# CH32X315CCU-R0.net
KiCad netlist of a schematic drawn in Altium Designer
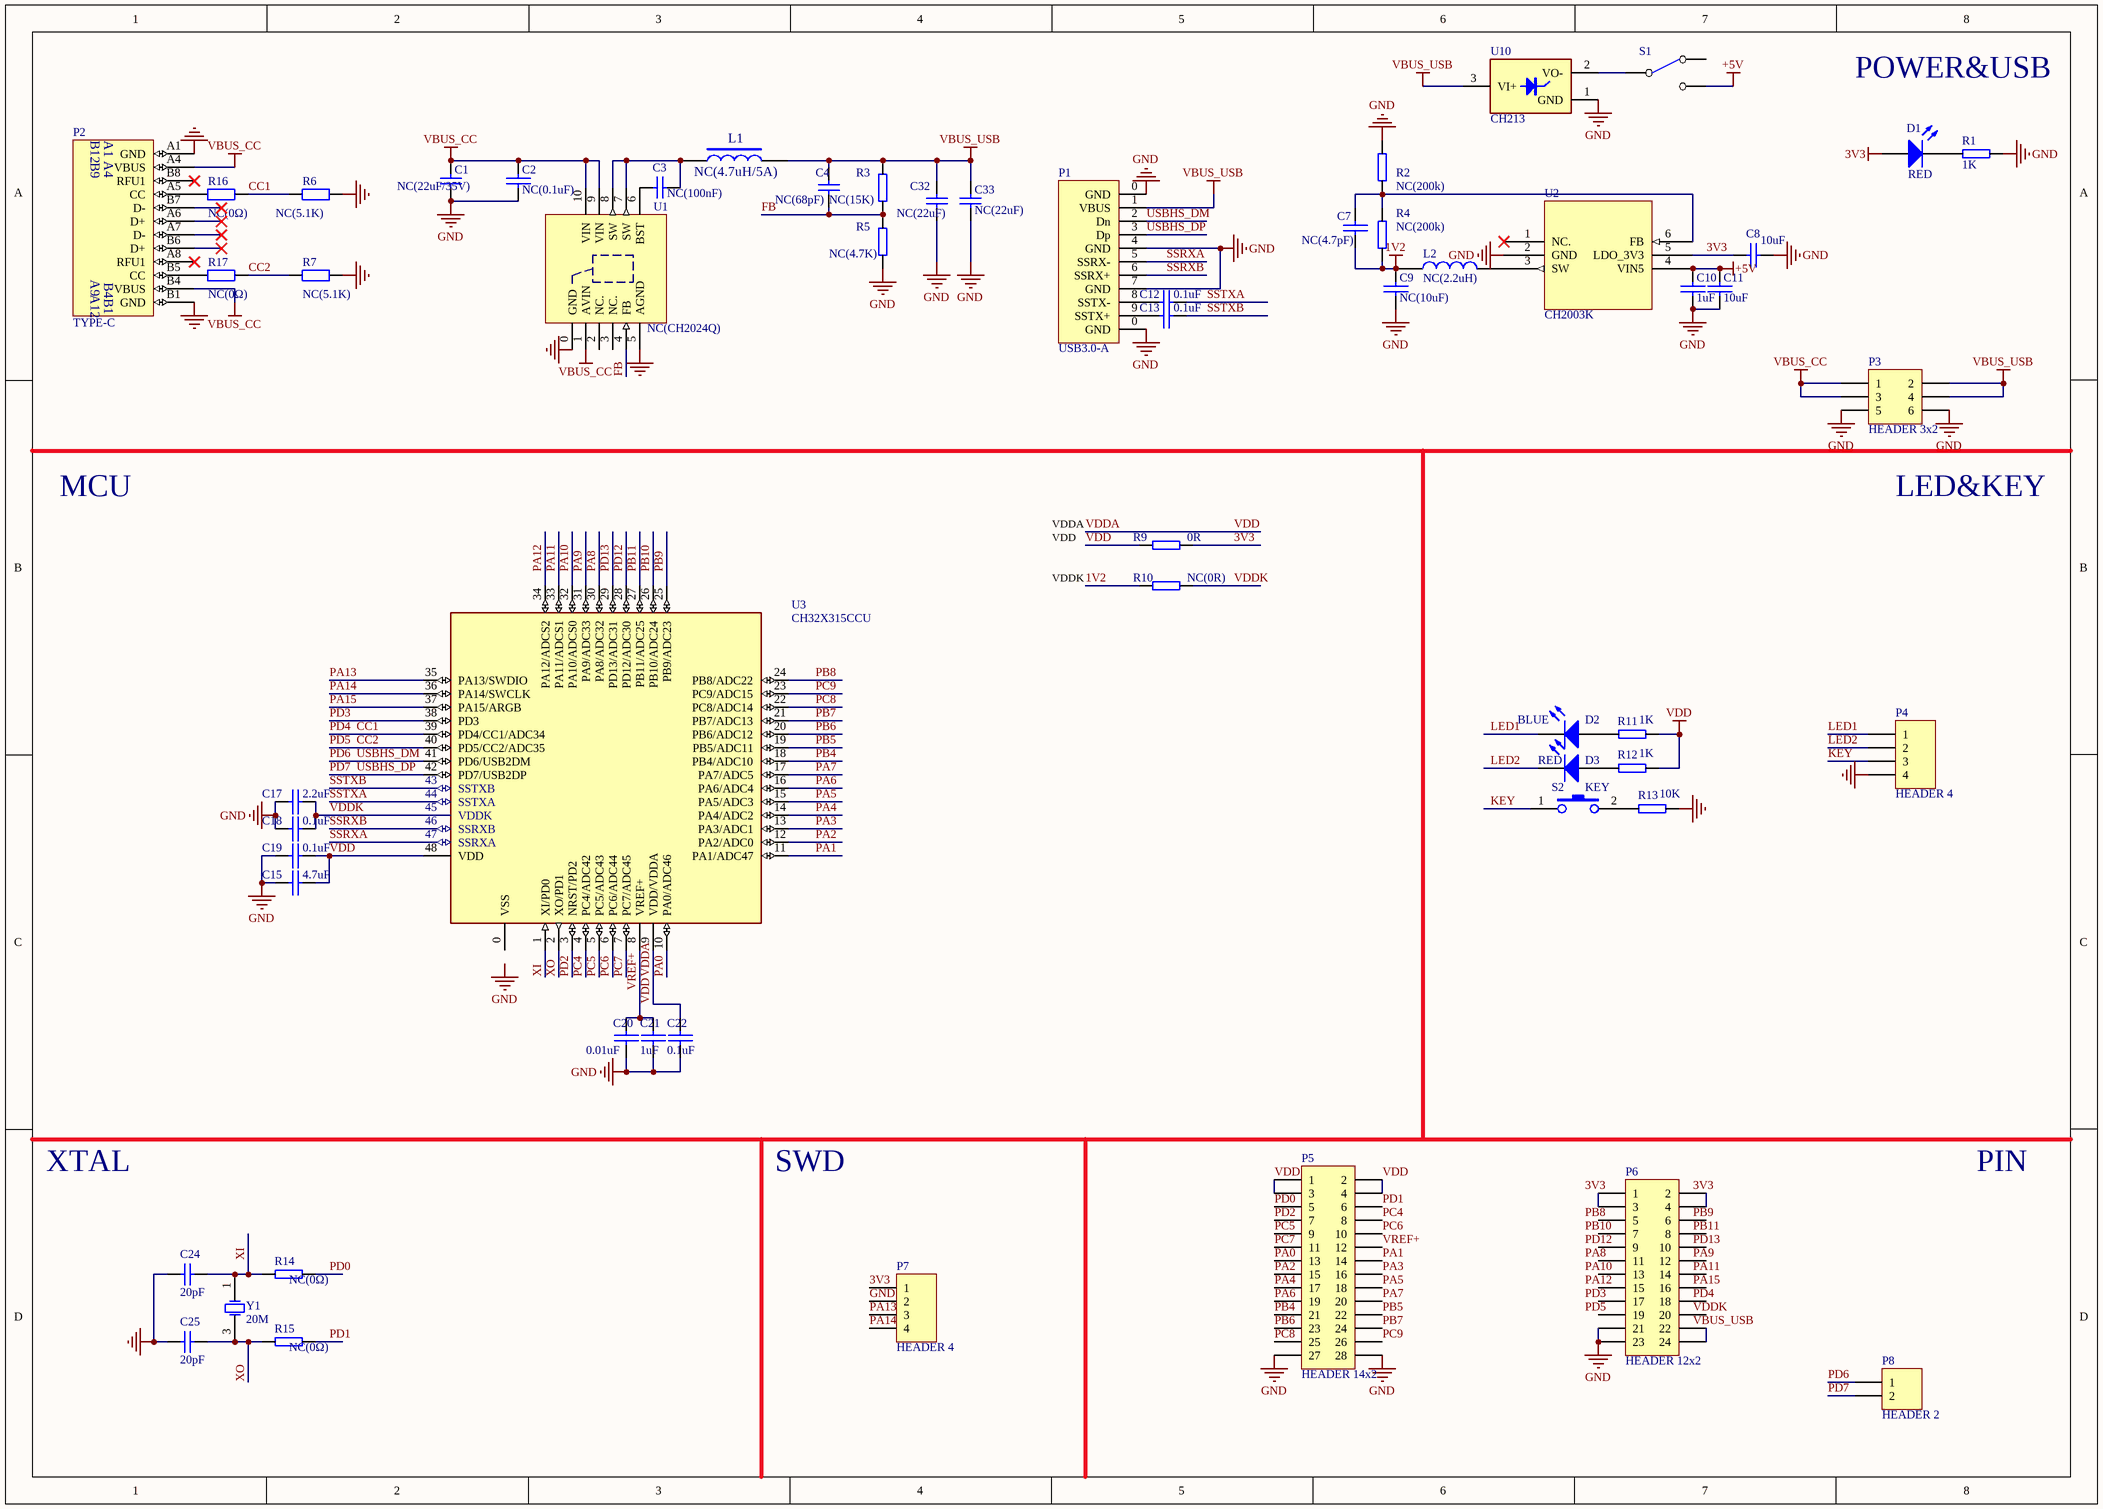
[diagram p0: CH32X315CCU-R0.SchDoc]

(export (version "E")
  (design (tool "Eeschema 10.0.6"))
  (components
    (comp (ref "C1")
      (value "NC(22uF/35V)")
      (footprint "0805_C")
      (description "贴片电容")
      (libsource (lib "Miscellaneous Devices LC") (part "0603 100nF (104) 10% 50V"))
    )
    (comp (ref "C2")
      (value "NC(0.1uF)")
      (footprint "0402_C")
      (description "Capacitor")
      (libsource (lib "*") (part "CAP"))
    )
    (comp (ref "C3")
      (value "NC(100nF)")
      (footprint "0402_C")
      (description "贴片电容")
      (libsource (lib "Miscellaneous Devices LC") (part "0603 1uF (105) 10% 50V"))
    )
    (comp (ref "C4")
      (value "NC(68pF)")
      (footprint "0402_C")
      (description "贴片电容")
      (libsource (lib "Miscellaneous Devices LC") (part "0603 100nF (104) 10% 50V"))
    )
    (comp (ref "C7")
      (value "NC(4.7pF)")
      (footprint "0402_C")
      (description "Capacitor")
      (libsource (lib "") (part "CAP_1"))
    )
    (comp (ref "C8")
      (value "10uF")
      (footprint "0603_C")
      (description "Capacitor")
      (libsource (lib "*") (part "CAP"))
    )
    (comp (ref "C9")
      (value "NC(10uF)")
      (footprint "0603_C")
      (description "Capacitor")
      (libsource (lib "*") (part "CAP"))
    )
    (comp (ref "C10")
      (value "1uF")
      (footprint "0402_C")
      (description "Capacitor")
      (libsource (lib "") (part "CAP_1"))
    )
    (comp (ref "C11")
      (value "10uF")
      (footprint "0603_C")
      (description "Capacitor")
      (libsource (lib "*") (part "CAP"))
    )
    (comp (ref "C12")
      (value "0.1uF")
      (footprint "0402_C")
      (description "Capacitor")
      (libsource (lib "*") (part "CAP"))
    )
    (comp (ref "C13")
      (value "0.1uF")
      (footprint "0402_C")
      (description "Capacitor")
      (libsource (lib "*") (part "CAP"))
    )
    (comp (ref "C15")
      (value "4.7uF")
      (footprint "0402_C")
      (description "Capacitor")
      (libsource (lib "") (part "CAP_1"))
    )
    (comp (ref "C17")
      (value "2.2uF")
      (footprint "0402_C")
      (description "Capacitor")
      (libsource (lib "") (part "CAP_1"))
    )
    (comp (ref "C18")
      (value "0.1uF")
      (footprint "0402_C")
      (description "Capacitor")
      (libsource (lib "") (part "CAP_1"))
    )
    (comp (ref "C19")
      (value "0.1uF")
      (footprint "0402_C")
      (description "Capacitor")
      (libsource (lib "") (part "CAP_1"))
    )
    (comp (ref "C20")
      (value "0.01uF")
      (footprint "0402_C")
      (description "Capacitor")
      (libsource (lib "") (part "CAP_1"))
    )
    (comp (ref "C21")
      (value "1uF")
      (footprint "0402_C")
      (description "Capacitor")
      (libsource (lib "") (part "CAP_1"))
    )
    (comp (ref "C22")
      (value "0.1uF")
      (footprint "0402_C")
      (description "Capacitor")
      (libsource (lib "") (part "CAP_1"))
    )
    (comp (ref "C24")
      (value "20pF")
      (footprint "0402_C")
      (description "Capacitor")
      (libsource (lib "Miscellaneous Devices") (part "Cap"))
    )
    (comp (ref "C25")
      (value "20pF")
      (footprint "0402_C")
      (description "Capacitor")
      (libsource (lib "Miscellaneous Devices") (part "Cap"))
    )
    (comp (ref "C32")
      (value "NC(22uF)")
      (footprint "0805_C")
      (description "贴片电容")
      (libsource (lib "Miscellaneous Devices LC") (part "0603 100nF (104) 10% 50V"))
    )
    (comp (ref "C33")
      (value "NC(22uF)")
      (footprint "0805_C")
      (description "贴片电容")
      (libsource (lib "Miscellaneous Devices LC") (part "0603 100nF (104) 10% 50V"))
    )
    (comp (ref "D1")
      (value "RED")
      (footprint "0603+")
      (description "Typical INFRARED GaAs LED")
      (fields (field (name "PUBLISHER") "Altium Limited"))
      (libsource (lib "*") (part "LED0"))
    )
    (comp (ref "D2")
      (value "BLUE")
      (footprint "0603+")
      (description "Typical INFRARED GaAs LED")
      (fields (field (name "PUBLISHER") "Altium Limited"))
      (libsource (lib "*") (part "LED0"))
    )
    (comp (ref "D3")
      (value "RED")
      (footprint "0603+")
      (description "Typical INFRARED GaAs LED")
      (fields (field (name "PUBLISHER") "Altium Limited"))
      (libsource (lib "*") (part "LED0"))
    )
    (comp (ref "L1")
      (value "NC(4.7uH/5A)")
      (footprint "IND-SMD_L7.0-W6.6")
      (libsource (lib "wch_sch_others") (part "INDUCTOR"))
    )
    (comp (ref "L2") (value "NC(2.2uH)") (footprint "CD32") (libsource (lib "*") (part "INDUCTOR")))
    (comp (ref "P1")
      (value "USB3.0-A")
      (footprint "USB3.0-A-Receptacle")
      (libsource (lib "wch_sch_others") (part "USB3.0-A"))
    )
    (comp (ref "P2")
      (value "TYPE-C")
      (footprint "TYPE-C-Receptacle-2.0")
      (libsource (lib "*") (part "TYPE-C1"))
    )
    (comp (ref "P3")
      (value "HEADER 3x2")
      (footprint "MYPCB:IDC6-2.54mm")
      (description "Header, 3-Pin, Dual row")
      (libsource (lib "wch_sch_others") (part "HEADER 3x2"))
    )
    (comp (ref "P4")
      (value "HEADER 4")
      (footprint "SIP4-2.54mm")
      (description "Header, 4-Pin")
      (libsource (lib "wch_sch_others") (part "HEADER 4"))
    )
    (comp (ref "P5")
      (value "HEADER 14x2")
      (footprint "MYPCB:IDC28-2.54MM")
      (description "Header, 14-Pin, Dual row")
      (libsource (lib "wch_sch_others") (part "HEADER 14x2"))
    )
    (comp (ref "P6")
      (value "HEADER 12x2")
      (footprint "MYPCB:IDC24-2.54MM")
      (description "Header, 12-Pin, Dual row")
      (libsource (lib "wch_sch_others") (part "HEADER 12x2"))
    )
    (comp (ref "P7")
      (value "HEADER 4")
      (footprint "SIP4-2.54mm")
      (description "Header, 4-Pin")
      (libsource (lib "wch_sch_others") (part "HEADER 4"))
    )
    (comp (ref "P8")
      (value "HEADER 2")
      (footprint "MYPCB:SIP2-2.54mm")
      (description "Header, 2-Pin")
      (libsource (lib "wch_sch_others") (part "HEADER 2"))
    )
    (comp (ref "R1") (value "1K") (footprint "0402") (libsource (lib "wch_sch_others") (part "RES")))
    (comp (ref "R2") (value "NC(200k)") (footprint "0402") (libsource (lib "") (part "RES_1")))
    (comp (ref "R3") (value "NC(15K)") (footprint "0402") (libsource (lib "wch_sch_others(1)") (part "RES")))
    (comp (ref "R4") (value "NC(200k)") (footprint "0402") (libsource (lib "") (part "RES_1")))
    (comp (ref "R5") (value "NC(4.7K)") (footprint "0402") (libsource (lib "wch_sch_others(1)") (part "RES")))
    (comp (ref "R6")
      (value "NC(5.1K)")
      (footprint "0402")
      (description "Resistor")
      (libsource (lib "Miscellaneous Devices") (part "Res2"))
    )
    (comp (ref "R7")
      (value "NC(5.1K)")
      (footprint "0402")
      (description "Resistor")
      (libsource (lib "Miscellaneous Devices") (part "Res2"))
    )
    (comp (ref "R9") (value "0R") (footprint "0402") (libsource (lib "*") (part "R")))
    (comp (ref "R10") (value "NC(0R)") (footprint "0402") (libsource (lib "*") (part "R")))
    (comp (ref "R11") (value "1K") (footprint "0402") (libsource (lib "wch_sch_others") (part "RES")))
    (comp (ref "R12") (value "1K") (footprint "0402") (libsource (lib "wch_sch_others") (part "RES")))
    (comp (ref "R13") (value "10K") (footprint "0402") (libsource (lib "wch_sch_others") (part "RES")))
    (comp (ref "R14") (value "NC(0Ω)") (footprint "0402") (libsource (lib "") (part "RES_1")))
    (comp (ref "R15") (value "NC(0Ω)") (footprint "0402") (libsource (lib "") (part "RES_1")))
    (comp (ref "R16")
      (value "NC(0Ω)")
      (footprint "0402")
      (description "Resistor")
      (libsource (lib "Miscellaneous Devices") (part "Res2"))
    )
    (comp (ref "R17")
      (value "NC(0Ω)")
      (footprint "0402")
      (description "Resistor")
      (libsource (lib "Miscellaneous Devices") (part "Res2"))
    )
    (comp (ref "S1") (value "SW SPDT") (footprint "SW1") (libsource (lib "*") (part "SW SPDT")))
    (comp (ref "S2")
      (value "KEY")
      (footprint "SMD_6.1x3.65x2.5mm-KEY")
      (libsource (lib "wch_sch_others") (part "KEY1"))
    )
    (comp (ref "U1")
      (value "NC(CH2024Q)")
      (footprint "DFN10_3X3")
      (description "Step-Down DC-DC Converter, 28V input, FB 1.2V, 3A output")
      (libsource (lib "DHXXXSCH") (part "CH2024Q"))
    )
    (comp (ref "U2")
      (value "CH2003K")
      (footprint "SOT-23-6")
      (description "Step-Down DC-DC Converter, 5V input, FB 0.6V, 800mA output, with LDO 3.3V * 200mA")
      (libsource (lib "DHXXXSCH") (part "CH2003K"))
    )
    (comp (ref "U3")
      (value "CH32X315CCU")
      (footprint "QFN48_5X5")
      (description "RISC-V FPU MCU, 417MHz, USB3.0_5Gbps, PD, HSADC")
      (libsource (lib "DHXXXSCH") (part "CH32X315CCU"))
    )
    (comp (ref "U10")
      (value "CH213")
      (footprint "SOT-23-3")
      (description "Ideal Diode 5V*1A")
      (libsource (lib "CHXXX") (part "CH213E"))
    )
    (comp (ref "Y1")
      (value "20M")
      (footprint "XT3225")
      (description "Crystal Oscillator")
      (fields (field (name "PUBLISHER") "Altium Limited"))
      (libsource (lib "Miscellaneous Devices") (part "XTAL"))
    )
  )
  (nets
    (net (code "1") (name "+5V") (class "Default")
      (node (ref "C10") (pin "2") (pinfunction "2_2") (pintype "passive"))
      (node (ref "C11") (pin "2") (pinfunction "2_2") (pintype "passive"))
      (node (ref "S1") (pin "2") (pinfunction "NC_2") (pintype "passive"))
      (node (ref "U2") (pin "4") (pinfunction "VIN5_4") (pintype "power_in"))
    )
    (net (code "3") (name "/CC1") (class "Default")
      (node (ref "R16") (pin "2") (pinfunction "2_2") (pintype "passive"))
      (node (ref "R6") (pin "1") (pinfunction "1_1") (pintype "passive"))
      (node (ref "U3") (pin "39") (pinfunction "PD4/CC1/ADC34_39") (pintype "bidirectional"))
    )
    (net (code "4") (name "/CC2") (class "Default")
      (node (ref "R17") (pin "2") (pinfunction "2_2") (pintype "passive"))
      (node (ref "R7") (pin "1") (pinfunction "1_1") (pintype "passive"))
      (node (ref "U3") (pin "40") (pinfunction "PD5/CC2/ADC35_40") (pintype "bidirectional"))
    )
    (net (code "5") (name "/FB") (class "Default")
      (node (ref "C4") (pin "2") (pinfunction "2_2") (pintype "passive"))
      (node (ref "R3") (pin "1") (pintype "passive"))
      (node (ref "R5") (pin "2") (pintype "passive"))
      (node (ref "U1") (pin "4") (pinfunction "FB_4") (pintype "input"))
    )
    (net (code "6") (name "/KEY") (class "Default")
      (node (ref "P4") (pin "3") (pinfunction "3_3") (pintype "passive"))
      (node (ref "S2") (pin "1") (pinfunction "1_1") (pintype "passive"))
    )
    (net (code "7") (name "/LED1") (class "Default")
      (node (ref "D2") (pin "2") (pinfunction "K_2") (pintype "passive"))
      (node (ref "P4") (pin "1") (pinfunction "1_1") (pintype "passive"))
    )
    (net (code "8") (name "/LED2") (class "Default")
      (node (ref "D3") (pin "2") (pinfunction "K_2") (pintype "passive"))
      (node (ref "P4") (pin "2") (pinfunction "2_2") (pintype "passive"))
    )
    (net (code "9") (name "/PA0") (class "Default")
      (node (ref "P5") (pin "13") (pinfunction "13_13") (pintype "passive"))
      (node (ref "U3") (pin "10") (pinfunction "PA0/ADC46_10") (pintype "bidirectional"))
    )
    (net (code "10") (name "/PA1") (class "Default")
      (node (ref "P5") (pin "14") (pinfunction "14_14") (pintype "passive"))
      (node (ref "U3") (pin "11") (pinfunction "PA1/ADC47_11") (pintype "bidirectional"))
    )
    (net (code "11") (name "/PA2") (class "Default")
      (node (ref "P5") (pin "15") (pinfunction "15_15") (pintype "passive"))
      (node (ref "U3") (pin "12") (pinfunction "PA2/ADC0_12") (pintype "bidirectional"))
    )
    (net (code "12") (name "/PA3") (class "Default")
      (node (ref "P5") (pin "16") (pinfunction "16_16") (pintype "passive"))
      (node (ref "U3") (pin "13") (pinfunction "PA3/ADC1_13") (pintype "bidirectional"))
    )
    (net (code "13") (name "/PA4") (class "Default")
      (node (ref "P5") (pin "17") (pinfunction "17_17") (pintype "passive"))
      (node (ref "U3") (pin "14") (pinfunction "PA4/ADC2_14") (pintype "bidirectional"))
    )
    (net (code "14") (name "/PA5") (class "Default")
      (node (ref "P5") (pin "18") (pinfunction "18_18") (pintype "passive"))
      (node (ref "U3") (pin "15") (pinfunction "PA5/ADC3_15") (pintype "bidirectional"))
    )
    (net (code "15") (name "/PA6") (class "Default")
      (node (ref "P5") (pin "19") (pinfunction "19_19") (pintype "passive"))
      (node (ref "U3") (pin "16") (pinfunction "PA6/ADC4_16") (pintype "bidirectional"))
    )
    (net (code "16") (name "/PA7") (class "Default")
      (node (ref "P5") (pin "20") (pinfunction "20_20") (pintype "passive"))
      (node (ref "U3") (pin "17") (pinfunction "PA7/ADC5_17") (pintype "bidirectional"))
    )
    (net (code "17") (name "/PA8") (class "Default")
      (node (ref "U3") (pin "30") (pinfunction "PA8/ADC32_30") (pintype "bidirectional"))
    )
    (net (code "18") (name "/PA9") (class "Default")
      (node (ref "U3") (pin "31") (pinfunction "PA9/ADC33_31") (pintype "bidirectional"))
    )
    (net (code "19") (name "/PA10") (class "Default")
      (node (ref "U3") (pin "32") (pinfunction "PA10/ADCS0_32") (pintype "bidirectional"))
    )
    (net (code "20") (name "/PA11") (class "Default")
      (node (ref "U3") (pin "33") (pinfunction "PA11/ADCS1_33") (pintype "bidirectional"))
    )
    (net (code "21") (name "/PA12") (class "Default")
      (node (ref "U3") (pin "34") (pinfunction "PA12/ADCS2_34") (pintype "bidirectional"))
    )
    (net (code "22") (name "/PA13") (class "Default")
      (node (ref "P7") (pin "3") (pinfunction "3_3") (pintype "passive"))
      (node (ref "U3") (pin "35") (pinfunction "PA13/SWDIO_35") (pintype "bidirectional"))
    )
    (net (code "23") (name "/PA14") (class "Default")
      (node (ref "P7") (pin "4") (pinfunction "4_4") (pintype "passive"))
      (node (ref "U3") (pin "36") (pinfunction "PA14/SWCLK_36") (pintype "bidirectional"))
    )
    (net (code "24") (name "/PA15") (class "Default")
      (node (ref "U3") (pin "37") (pinfunction "PA15/ARGB_37") (pintype "bidirectional"))
    )
    (net (code "25") (name "/PB4") (class "Default")
      (node (ref "P5") (pin "21") (pinfunction "21_21") (pintype "passive"))
      (node (ref "U3") (pin "18") (pinfunction "PB4/ADC10_18") (pintype "bidirectional"))
    )
    (net (code "26") (name "/PB5") (class "Default")
      (node (ref "P5") (pin "22") (pinfunction "22_22") (pintype "passive"))
      (node (ref "U3") (pin "19") (pinfunction "PB5/ADC11_19") (pintype "bidirectional"))
    )
    (net (code "27") (name "/PB6") (class "Default")
      (node (ref "P5") (pin "23") (pinfunction "23_23") (pintype "passive"))
      (node (ref "U3") (pin "20") (pinfunction "PB6/ADC12_20") (pintype "bidirectional"))
    )
    (net (code "28") (name "/PB7") (class "Default")
      (node (ref "P5") (pin "24") (pinfunction "24_24") (pintype "passive"))
      (node (ref "U3") (pin "21") (pinfunction "PB7/ADC13_21") (pintype "bidirectional"))
    )
    (net (code "29") (name "/PB8") (class "Default")
      (node (ref "U3") (pin "24") (pinfunction "PB8/ADC22_24") (pintype "bidirectional"))
    )
    (net (code "30") (name "/PB9") (class "Default")
      (node (ref "U3") (pin "25") (pinfunction "PB9/ADC23_25") (pintype "bidirectional"))
    )
    (net (code "31") (name "/PB10") (class "Default")
      (node (ref "U3") (pin "26") (pinfunction "PB10/ADC24_26") (pintype "bidirectional"))
    )
    (net (code "32") (name "/PB11") (class "Default")
      (node (ref "U3") (pin "27") (pinfunction "PB11/ADC25_27") (pintype "bidirectional"))
    )
    (net (code "33") (name "/PC4") (class "Default")
      (node (ref "P5") (pin "8") (pinfunction "8_8") (pintype "passive"))
      (node (ref "U3") (pin "4") (pinfunction "PC4/ADC42_4") (pintype "bidirectional"))
    )
    (net (code "34") (name "/PC5") (class "Default")
      (node (ref "P5") (pin "9") (pinfunction "9_9") (pintype "passive"))
      (node (ref "U3") (pin "5") (pinfunction "PC5/ADC43_5") (pintype "bidirectional"))
    )
    (net (code "35") (name "/PC6") (class "Default")
      (node (ref "P5") (pin "10") (pinfunction "10_10") (pintype "passive"))
      (node (ref "U3") (pin "6") (pinfunction "PC6/ADC44_6") (pintype "bidirectional"))
    )
    (net (code "36") (name "/PC7") (class "Default")
      (node (ref "P5") (pin "11") (pinfunction "11_11") (pintype "passive"))
      (node (ref "U3") (pin "7") (pinfunction "PC7/ADC45_7") (pintype "bidirectional"))
    )
    (net (code "37") (name "/PC8") (class "Default")
      (node (ref "P5") (pin "25") (pinfunction "25_25") (pintype "passive"))
      (node (ref "U3") (pin "22") (pinfunction "PC8/ADC14_22") (pintype "bidirectional"))
    )
    (net (code "38") (name "/PC9") (class "Default")
      (node (ref "P5") (pin "26") (pinfunction "26_26") (pintype "passive"))
      (node (ref "U3") (pin "23") (pinfunction "PC9/ADC15_23") (pintype "bidirectional"))
    )
    (net (code "39") (name "/PD0") (class "Default")
      (node (ref "P5") (pin "5") (pinfunction "5_5") (pintype "passive"))
      (node (ref "R14") (pin "1") (pintype "passive"))
    )
    (net (code "40") (name "/PD1") (class "Default")
      (node (ref "P5") (pin "6") (pinfunction "6_6") (pintype "passive"))
      (node (ref "R15") (pin "1") (pintype "passive"))
    )
    (net (code "41") (name "/PD2") (class "Default")
      (node (ref "P5") (pin "7") (pinfunction "7_7") (pintype "passive"))
      (node (ref "U3") (pin "3") (pinfunction "NRST/PD2_3") (pintype "bidirectional"))
    )
    (net (code "42") (name "/PD3") (class "Default")
      (node (ref "U3") (pin "38") (pinfunction "PD3_38") (pintype "bidirectional"))
    )
    (net (code "43") (name "/PD6") (class "Default")
      (node (ref "P1") (pin "2") (pinfunction "Dn_2") (pintype "passive"))
      (node (ref "P8") (pin "1") (pinfunction "1_1") (pintype "passive"))
      (node (ref "U3") (pin "41") (pinfunction "PD6/USB2DM_41") (pintype "bidirectional"))
    )
    (net (code "44") (name "/PD7") (class "Default")
      (node (ref "P1") (pin "3") (pinfunction "Dp_3") (pintype "passive"))
      (node (ref "P8") (pin "2") (pinfunction "2_2") (pintype "passive"))
      (node (ref "U3") (pin "42") (pinfunction "PD7/USB2DP_42") (pintype "bidirectional"))
    )
    (net (code "45") (name "/PD12") (class "Default")
      (node (ref "U3") (pin "28") (pinfunction "PD12/ADC30_28") (pintype "bidirectional"))
    )
    (net (code "46") (name "/PD13") (class "Default")
      (node (ref "U3") (pin "29") (pinfunction "PD13/ADC31_29") (pintype "bidirectional"))
    )
    (net (code "47") (name "/SSRXA") (class "Default")
      (node (ref "P1") (pin "5") (pinfunction "SSRX-_5") (pintype "passive"))
      (node (ref "U3") (pin "47") (pinfunction "SSRXA_47") (pintype "bidirectional"))
    )
    (net (code "48") (name "/SSRXB") (class "Default")
      (node (ref "P1") (pin "6") (pinfunction "SSRX+_6") (pintype "passive"))
      (node (ref "U3") (pin "46") (pinfunction "SSRXB_46") (pintype "bidirectional"))
    )
    (net (code "49") (name "/SSTXA") (class "Default")
      (node (ref "C12") (pin "2") (pinfunction "2_2") (pintype "passive"))
      (node (ref "U3") (pin "44") (pinfunction "SSTXA_44") (pintype "bidirectional"))
    )
    (net (code "50") (name "/SSTXB") (class "Default")
      (node (ref "C13") (pin "2") (pinfunction "2_2") (pintype "passive"))
      (node (ref "U3") (pin "43") (pinfunction "SSTXB_43") (pintype "bidirectional"))
    )
    (net (code "51") (name "/VDDK") (class "Default")
      (node (ref "C17") (pin "1") (pinfunction "1_1") (pintype "passive"))
      (node (ref "C18") (pin "1") (pinfunction "1_1") (pintype "passive"))
      (node (ref "R10") (pin "1") (pinfunction "1_1") (pintype "passive"))
      (node (ref "U3") (pin "45") (pinfunction "VDDK_45") (pintype "power_in"))
    )
    (net (code "52") (name "/VREF+") (class "Default")
      (node (ref "C20") (pin "1") (pinfunction "1_1") (pintype "passive"))
      (node (ref "C21") (pin "1") (pinfunction "1_1") (pintype "passive"))
      (node (ref "P5") (pin "12") (pinfunction "12_12") (pintype "passive"))
      (node (ref "U3") (pin "8") (pinfunction "VREF+_8") (pintype "power_in"))
    )
    (net (code "53") (name "/XI") (class "Default")
      (node (ref "C24") (pin "1") (pinfunction "1_1") (pintype "passive"))
      (node (ref "R14") (pin "2") (pintype "passive"))
      (node (ref "U3") (pin "1") (pinfunction "XI/PD0_1") (pintype "input"))
      (node (ref "Y1") (pin "1") (pinfunction "OSC1_1") (pintype "passive"))
    )
    (net (code "54") (name "/XO") (class "Default")
      (node (ref "C25") (pin "1") (pinfunction "1_1") (pintype "passive"))
      (node (ref "R15") (pin "2") (pintype "passive"))
      (node (ref "U3") (pin "2") (pinfunction "XO/PD1_2") (pintype "output"))
      (node (ref "Y1") (pin "3") (pinfunction "OSC2_3") (pintype "passive"))
    )
    (net (code "55") (name "1V2") (class "Default")
      (node (ref "C7") (pin "1") (pinfunction "1_1") (pintype "passive"))
      (node (ref "C9") (pin "2") (pinfunction "2_2") (pintype "passive"))
      (node (ref "L2") (pin "2") (pinfunction "2_2") (pintype "passive"))
      (node (ref "R10") (pin "2") (pinfunction "2_2") (pintype "passive"))
      (node (ref "R4") (pin "1") (pintype "passive"))
    )
    (net (code "56") (name "3V3") (class "Default")
      (node (ref "C8") (pin "2") (pinfunction "2_2") (pintype "passive"))
      (node (ref "D1") (pin "1") (pinfunction "A_1") (pintype "passive"))
      (node (ref "P7") (pin "1") (pinfunction "1_1") (pintype "passive"))
      (node (ref "R9") (pin "1") (pinfunction "1_1") (pintype "passive"))
      (node (ref "U2") (pin "5") (pinfunction "LDO_3V3_5") (pintype "power_in"))
    )
    (net (code "57") (name "GND") (class "Default")
      (node (ref "C1") (pin "1") (pinfunction "1_1") (pintype "passive"))
      (node (ref "C10") (pin "1") (pinfunction "1_1") (pintype "passive"))
      (node (ref "C11") (pin "1") (pinfunction "1_1") (pintype "passive"))
      (node (ref "C15") (pin "2") (pinfunction "2_2") (pintype "passive"))
      (node (ref "C17") (pin "2") (pinfunction "2_2") (pintype "passive"))
      (node (ref "C18") (pin "2") (pinfunction "2_2") (pintype "passive"))
      (node (ref "C19") (pin "2") (pinfunction "2_2") (pintype "passive"))
      (node (ref "C2") (pin "1") (pinfunction "1_1") (pintype "passive"))
      (node (ref "C20") (pin "2") (pinfunction "2_2") (pintype "passive"))
      (node (ref "C21") (pin "2") (pinfunction "2_2") (pintype "passive"))
      (node (ref "C22") (pin "2") (pinfunction "2_2") (pintype "passive"))
      (node (ref "C24") (pin "2") (pinfunction "2_2") (pintype "passive"))
      (node (ref "C25") (pin "2") (pinfunction "2_2") (pintype "passive"))
      (node (ref "C32") (pin "1") (pinfunction "1_1") (pintype "passive"))
      (node (ref "C33") (pin "1") (pinfunction "1_1") (pintype "passive"))
      (node (ref "C8") (pin "1") (pinfunction "1_1") (pintype "passive"))
      (node (ref "C9") (pin "1") (pinfunction "1_1") (pintype "passive"))
      (node (ref "P1") (pin "0") (pinfunction "GND_0") (pintype "passive"))
      (node (ref "P1") (pin "4") (pinfunction "GND_4") (pintype "passive"))
      (node (ref "P1") (pin "7") (pinfunction "GND_7") (pintype "passive"))
      (node (ref "P2") (pin "A1") (pinfunction "GND_A1") (pintype "bidirectional"))
      (node (ref "P2") (pin "B1") (pinfunction "GND_B1") (pintype "bidirectional"))
      (node (ref "P3") (pin "5") (pinfunction "5_5") (pintype "passive"))
      (node (ref "P3") (pin "6") (pinfunction "6_6") (pintype "passive"))
      (node (ref "P4") (pin "4") (pinfunction "4_4") (pintype "passive"))
      (node (ref "P5") (pin "27") (pinfunction "27_27") (pintype "passive"))
      (node (ref "P5") (pin "28") (pinfunction "28_28") (pintype "passive"))
      (node (ref "P6") (pin "21") (pinfunction "21_21") (pintype "passive"))
      (node (ref "P6") (pin "23") (pinfunction "23_23") (pintype "passive"))
      (node (ref "P7") (pin "2") (pinfunction "2_2") (pintype "passive"))
      (node (ref "R1") (pin "2") (pintype "passive"))
      (node (ref "R13") (pin "1") (pintype "passive"))
      (node (ref "R2") (pin "2") (pintype "passive"))
      (node (ref "R5") (pin "1") (pintype "passive"))
      (node (ref "R6") (pin "2") (pinfunction "2_2") (pintype "passive"))
      (node (ref "R7") (pin "2") (pinfunction "2_2") (pintype "passive"))
      (node (ref "U1") (pin "0") (pinfunction "GND_0") (pintype "power_in"))
      (node (ref "U1") (pin "5") (pinfunction "AGND_5") (pintype "power_in"))
      (node (ref "U10") (pin "1") (pinfunction "GND_1") (pintype "power_in"))
      (node (ref "U2") (pin "2") (pinfunction "GND_2") (pintype "power_in"))
    )
    (net (code "58") (name "Net-(C3-Pad2)") (class "Default")
      (node (ref "C3") (pin "2") (pinfunction "2_2") (pintype "passive"))
      (node (ref "L1") (pin "1") (pinfunction "1_1") (pintype "passive"))
      (node (ref "U1") (pin "7") (pinfunction "SW_7") (pintype "output"))
      (node (ref "U1") (pin "8") (pinfunction "SW_8") (pintype "output"))
    )
    (net (code "59") (name "Net-(D1-K)") (class "Default")
      (node (ref "D1") (pin "2") (pinfunction "K_2") (pintype "passive"))
      (node (ref "R1") (pin "1") (pintype "passive"))
    )
    (net (code "60") (name "Net-(D2-A)") (class "Default")
      (node (ref "D2") (pin "1") (pinfunction "A_1") (pintype "passive"))
      (node (ref "R11") (pin "2") (pintype "passive"))
    )
    (net (code "61") (name "Net-(D3-A)") (class "Default")
      (node (ref "D3") (pin "1") (pinfunction "A_1") (pintype "passive"))
      (node (ref "R12") (pin "2") (pintype "passive"))
    )
    (net (code "62") (name "Net-(P1-SSTX+)") (class "Default")
      (node (ref "C13") (pin "1") (pinfunction "1_1") (pintype "passive"))
      (node (ref "P1") (pin "9") (pinfunction "SSTX+_9") (pintype "passive"))
    )
    (net (code "63") (name "Net-(P1-SSTX-)") (class "Default")
      (node (ref "C12") (pin "1") (pinfunction "1_1") (pintype "passive"))
      (node (ref "P1") (pin "8") (pinfunction "SSTX-_8") (pintype "passive"))
    )
    (net (code "64") (name "Net-(P2-CC-PadA5)") (class "Default")
      (node (ref "P2") (pin "A5") (pinfunction "CC_A5") (pintype "bidirectional"))
      (node (ref "R16") (pin "1") (pinfunction "1_1") (pintype "passive"))
    )
    (net (code "65") (name "Net-(P2-CC-PadB5)") (class "Default")
      (node (ref "P2") (pin "B5") (pinfunction "CC_B5") (pintype "bidirectional"))
      (node (ref "R17") (pin "1") (pinfunction "1_1") (pintype "passive"))
    )
    (net (code "66") (name "Net-(P6-Pad1)") (class "Default")
      (node (ref "P6") (pin "1") (pinfunction "1_1") (pintype "passive"))
      (node (ref "P6") (pin "3") (pinfunction "3_3") (pintype "passive"))
    )
    (net (code "67") (name "Net-(P6-Pad2)") (class "Default")
      (node (ref "P6") (pin "2") (pinfunction "2_2") (pintype "passive"))
      (node (ref "P6") (pin "4") (pinfunction "4_4") (pintype "passive"))
    )
    (net (code "68") (name "Net-(P6-Pad22)") (class "Default")
      (node (ref "P6") (pin "22") (pinfunction "22_22") (pintype "passive"))
      (node (ref "P6") (pin "24") (pinfunction "24_24") (pintype "passive"))
    )
    (net (code "69") (name "Net-(R13-Pad2)") (class "Default")
      (node (ref "R13") (pin "2") (pintype "passive"))
      (node (ref "S2") (pin "2") (pinfunction "2_2") (pintype "passive"))
    )
    (net (code "70") (name "Net-(S1-COMMON)") (class "Default")
      (node (ref "S1") (pin "1") (pinfunction "COMMON_1") (pintype "passive"))
      (node (ref "U10") (pin "2") (pinfunction "VO-_2") (pintype "power_in"))
    )
    (net (code "71") (name "Net-(U1-BST)") (class "Default")
      (node (ref "C3") (pin "1") (pinfunction "1_1") (pintype "passive"))
      (node (ref "U1") (pin "6") (pinfunction "BST_6") (pintype "power_in"))
    )
    (net (code "72") (name "Net-(U2-FB)") (class "Default")
      (node (ref "C7") (pin "2") (pinfunction "2_2") (pintype "passive"))
      (node (ref "R2") (pin "1") (pintype "passive"))
      (node (ref "R4") (pin "2") (pintype "passive"))
      (node (ref "U2") (pin "6") (pinfunction "FB_6") (pintype "input"))
    )
    (net (code "73") (name "Net-(U2-SW)") (class "Default")
      (node (ref "L2") (pin "1") (pinfunction "1_1") (pintype "passive"))
      (node (ref "U2") (pin "3") (pinfunction "SW_3") (pintype "output"))
    )
    (net (code "74") (name "VBUS_CC") (class "Default")
      (node (ref "C1") (pin "2") (pinfunction "2_2") (pintype "passive"))
      (node (ref "C2") (pin "2") (pinfunction "2_2") (pintype "passive"))
      (node (ref "P2") (pin "A4") (pinfunction "VBUS_A4") (pintype "bidirectional"))
      (node (ref "P2") (pin "B4") (pinfunction "VBUS_B4") (pintype "bidirectional"))
      (node (ref "P3") (pin "1") (pinfunction "1_1") (pintype "passive"))
      (node (ref "P3") (pin "3") (pinfunction "3_3") (pintype "passive"))
      (node (ref "U1") (pin "1") (pinfunction "AVIN_1") (pintype "power_in"))
      (node (ref "U1") (pin "10") (pinfunction "VIN_10") (pintype "power_in"))
      (node (ref "U1") (pin "9") (pinfunction "VIN_9") (pintype "power_in"))
    )
    (net (code "75") (name "VBUS_USB") (class "Default")
      (node (ref "C32") (pin "2") (pinfunction "2_2") (pintype "passive"))
      (node (ref "C33") (pin "2") (pinfunction "2_2") (pintype "passive"))
      (node (ref "C4") (pin "1") (pinfunction "1_1") (pintype "passive"))
      (node (ref "L1") (pin "2") (pinfunction "2_2") (pintype "passive"))
      (node (ref "P1") (pin "1") (pinfunction "VBUS_1") (pintype "passive"))
      (node (ref "P3") (pin "2") (pinfunction "2_2") (pintype "passive"))
      (node (ref "P3") (pin "4") (pinfunction "4_4") (pintype "passive"))
      (node (ref "R3") (pin "2") (pintype "passive"))
      (node (ref "U10") (pin "3") (pinfunction "VI+_3") (pintype "power_in"))
    )
    (net (code "76") (name "VDD") (class "Default")
      (node (ref "C15") (pin "1") (pinfunction "1_1") (pintype "passive"))
      (node (ref "C19") (pin "1") (pinfunction "1_1") (pintype "passive"))
      (node (ref "C22") (pin "1") (pinfunction "1_1") (pintype "passive"))
      (node (ref "P5") (pin "1") (pinfunction "1_1") (pintype "passive"))
      (node (ref "P5") (pin "2") (pinfunction "2_2") (pintype "passive"))
      (node (ref "P5") (pin "3") (pinfunction "3_3") (pintype "passive"))
      (node (ref "P5") (pin "4") (pinfunction "4_4") (pintype "passive"))
      (node (ref "R11") (pin "1") (pintype "passive"))
      (node (ref "R12") (pin "1") (pintype "passive"))
      (node (ref "R9") (pin "2") (pinfunction "2_2") (pintype "passive"))
      (node (ref "U3") (pin "48") (pinfunction "VDD_48") (pintype "power_in"))
      (node (ref "U3") (pin "9") (pinfunction "VDD/VDDA_9") (pintype "power_in"))
    )
    (net (code "77") (name "unconnected-(P2-D+-PadA6)") (class "Default")
      (node (ref "P2") (pin "A6") (pinfunction "D+_A6") (pintype "bidirectional+no_connect"))
    )
    (net (code "78") (name "unconnected-(P2-D+-PadB6)") (class "Default")
      (node (ref "P2") (pin "B6") (pinfunction "D+_B6") (pintype "bidirectional+no_connect"))
    )
    (net (code "79") (name "unconnected-(P2-D--PadA7)") (class "Default")
      (node (ref "P2") (pin "A7") (pinfunction "D-_A7") (pintype "bidirectional+no_connect"))
    )
    (net (code "80") (name "unconnected-(P2-D--PadB7)") (class "Default")
      (node (ref "P2") (pin "B7") (pinfunction "D-_B7") (pintype "bidirectional+no_connect"))
    )
    (net (code "81") (name "unconnected-(P2-RFU1-PadA8)") (class "Default")
      (node (ref "P2") (pin "A8") (pinfunction "RFU1_A8") (pintype "bidirectional+no_connect"))
    )
    (net (code "82") (name "unconnected-(P2-RFU1-PadB8)") (class "Default")
      (node (ref "P2") (pin "B8") (pinfunction "RFU1_B8") (pintype "bidirectional+no_connect"))
    )
    (net (code "83") (name "unconnected-(P6-Pad5)") (class "Default")
      (node (ref "P6") (pin "5") (pinfunction "5_5") (pintype "passive"))
    )
    (net (code "84") (name "unconnected-(P6-Pad6)") (class "Default")
      (node (ref "P6") (pin "6") (pinfunction "6_6") (pintype "passive"))
    )
    (net (code "85") (name "unconnected-(P6-Pad7)") (class "Default")
      (node (ref "P6") (pin "7") (pinfunction "7_7") (pintype "passive"))
    )
    (net (code "86") (name "unconnected-(P6-Pad8)") (class "Default")
      (node (ref "P6") (pin "8") (pinfunction "8_8") (pintype "passive"))
    )
    (net (code "87") (name "unconnected-(P6-Pad9)") (class "Default")
      (node (ref "P6") (pin "9") (pinfunction "9_9") (pintype "passive"))
    )
    (net (code "88") (name "unconnected-(P6-Pad10)") (class "Default")
      (node (ref "P6") (pin "10") (pinfunction "10_10") (pintype "passive"))
    )
    (net (code "89") (name "unconnected-(P6-Pad11)") (class "Default")
      (node (ref "P6") (pin "11") (pinfunction "11_11") (pintype "passive"))
    )
    (net (code "90") (name "unconnected-(P6-Pad12)") (class "Default")
      (node (ref "P6") (pin "12") (pinfunction "12_12") (pintype "passive"))
    )
    (net (code "91") (name "unconnected-(P6-Pad13)") (class "Default")
      (node (ref "P6") (pin "13") (pinfunction "13_13") (pintype "passive"))
    )
    (net (code "92") (name "unconnected-(P6-Pad14)") (class "Default")
      (node (ref "P6") (pin "14") (pinfunction "14_14") (pintype "passive"))
    )
    (net (code "93") (name "unconnected-(P6-Pad15)") (class "Default")
      (node (ref "P6") (pin "15") (pinfunction "15_15") (pintype "passive"))
    )
    (net (code "94") (name "unconnected-(P6-Pad16)") (class "Default")
      (node (ref "P6") (pin "16") (pinfunction "16_16") (pintype "passive"))
    )
    (net (code "95") (name "unconnected-(P6-Pad17)") (class "Default")
      (node (ref "P6") (pin "17") (pinfunction "17_17") (pintype "passive"))
    )
    (net (code "96") (name "unconnected-(P6-Pad18)") (class "Default")
      (node (ref "P6") (pin "18") (pinfunction "18_18") (pintype "passive"))
    )
    (net (code "97") (name "unconnected-(P6-Pad19)") (class "Default")
      (node (ref "P6") (pin "19") (pinfunction "19_19") (pintype "passive"))
    )
    (net (code "98") (name "unconnected-(P6-Pad20)") (class "Default")
      (node (ref "P6") (pin "20") (pinfunction "20_20") (pintype "passive"))
    )
    (net (code "99") (name "unconnected-(S1-NO-Pad3)") (class "Default")
      (node (ref "S1") (pin "3") (pinfunction "NO_3") (pintype "passive"))
    )
    (net (code "100") (name "unconnected-(U1-NC.-Pad2)") (class "Default")
      (node (ref "U1") (pin "2") (pinfunction "NC._2") (pintype "passive"))
    )
    (net (code "101") (name "unconnected-(U1-NC.-Pad3)") (class "Default")
      (node (ref "U1") (pin "3") (pinfunction "NC._3") (pintype "passive"))
    )
    (net (code "102") (name "unconnected-(U2-NC.-Pad1)") (class "Default")
      (node (ref "U2") (pin "1") (pinfunction "NC._1") (pintype "passive+no_connect"))
    )
    (net (code "103") (name "unconnected-(U3-VSS-Pad0)") (class "Default")
      (node (ref "U3") (pin "0") (pinfunction "VSS_0") (pintype "power_in"))
    )
  )
)
